# xytheta.net
KiCad netlist of a schematic drawn in EAGLE
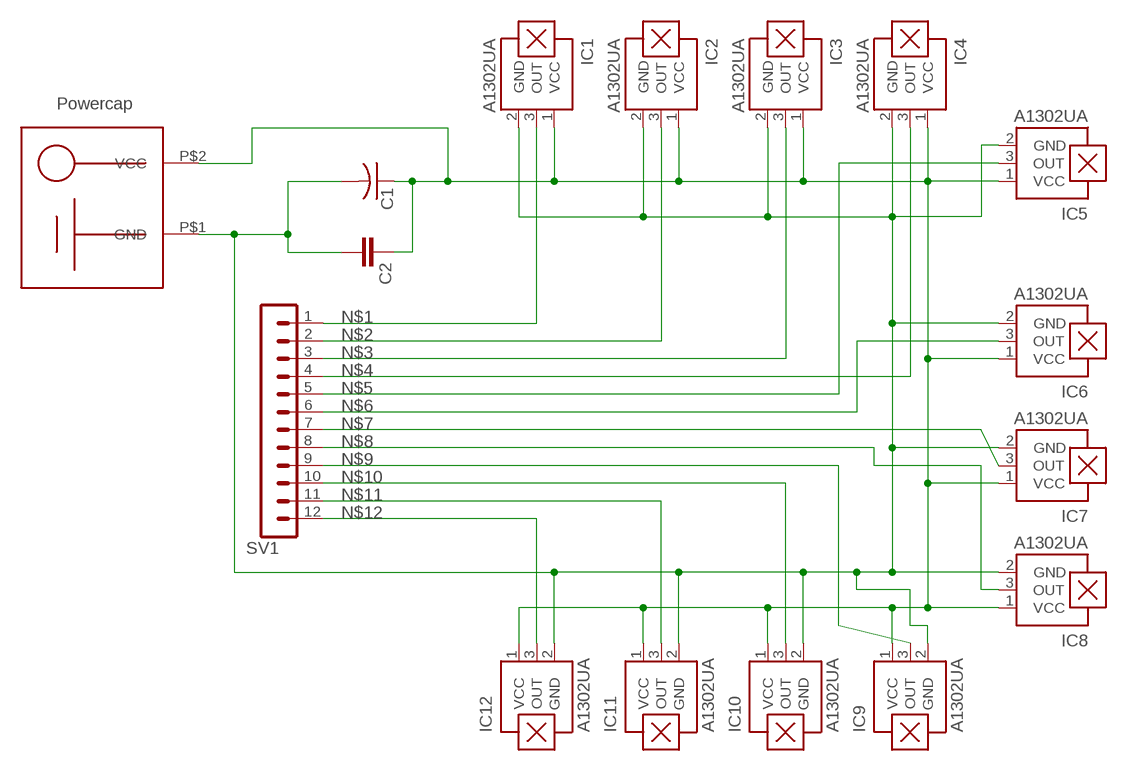
[diagram p0: schematic, sheet 1]

(export (version "E")
  (design (tool "Eeschema 10.0.6"))
  (components
    (comp (ref "C1")
      (value "C-US025-050X050")
      (footprint "eagle-import:C025-050X050")
      (libsource (lib "eagle-import") (part "C-US025-050X050"))
    )
    (comp (ref "C2")
      (value "C-EU025-025X050")
      (footprint "eagle-import:C025-025X050")
      (libsource (lib "eagle-import") (part "C-EU025-025X050"))
    )
    (comp (ref "IC1")
      (value "A1302UA")
      (footprint "eagle-import:SIP3-UA")
      (fields (field (name "MF") "ALLEGRO MICROSYSTEMS, INC.") (field (name "MPN") "A1302EUA-T"))
      (libsource (lib "eagle-import") (part "A13?UA02"))
    )
    (comp (ref "IC2")
      (value "A1302UA")
      (footprint "eagle-import:SIP3-UA")
      (fields (field (name "MF") "ALLEGRO MICROSYSTEMS, INC.") (field (name "MPN") "A1302EUA-T"))
      (libsource (lib "eagle-import") (part "A13?UA02"))
    )
    (comp (ref "IC3")
      (value "A1302UA")
      (footprint "eagle-import:SIP3-UA")
      (fields (field (name "MF") "ALLEGRO MICROSYSTEMS, INC.") (field (name "MPN") "A1302EUA-T"))
      (libsource (lib "eagle-import") (part "A13?UA02"))
    )
    (comp (ref "IC4")
      (value "A1302UA")
      (footprint "eagle-import:SIP3-UA")
      (fields (field (name "MF") "ALLEGRO MICROSYSTEMS, INC.") (field (name "MPN") "A1302EUA-T"))
      (libsource (lib "eagle-import") (part "A13?UA02"))
    )
    (comp (ref "IC5")
      (value "A1302UA")
      (footprint "eagle-import:SIP3-UA")
      (fields (field (name "MF") "ALLEGRO MICROSYSTEMS, INC.") (field (name "MPN") "A1302EUA-T"))
      (libsource (lib "eagle-import") (part "A13?UA02"))
    )
    (comp (ref "IC6")
      (value "A1302UA")
      (footprint "eagle-import:SIP3-UA")
      (fields (field (name "MF") "ALLEGRO MICROSYSTEMS, INC.") (field (name "MPN") "A1302EUA-T"))
      (libsource (lib "eagle-import") (part "A13?UA02"))
    )
    (comp (ref "IC7")
      (value "A1302UA")
      (footprint "eagle-import:SIP3-UA")
      (fields (field (name "MF") "ALLEGRO MICROSYSTEMS, INC.") (field (name "MPN") "A1302EUA-T"))
      (libsource (lib "eagle-import") (part "A13?UA02"))
    )
    (comp (ref "IC8")
      (value "A1302UA")
      (footprint "eagle-import:SIP3-UA")
      (fields (field (name "MF") "ALLEGRO MICROSYSTEMS, INC.") (field (name "MPN") "A1302EUA-T"))
      (libsource (lib "eagle-import") (part "A13?UA02"))
    )
    (comp (ref "IC9")
      (value "A1302UA")
      (footprint "eagle-import:SIP3-UA")
      (fields (field (name "MF") "ALLEGRO MICROSYSTEMS, INC.") (field (name "MPN") "A1302EUA-T"))
      (libsource (lib "eagle-import") (part "A13?UA02"))
    )
    (comp (ref "IC10")
      (value "A1302UA")
      (footprint "eagle-import:SIP3-UA")
      (fields (field (name "MF") "ALLEGRO MICROSYSTEMS, INC.") (field (name "MPN") "A1302EUA-T"))
      (libsource (lib "eagle-import") (part "A13?UA02"))
    )
    (comp (ref "IC11")
      (value "A1302UA")
      (footprint "eagle-import:SIP3-UA")
      (fields (field (name "MF") "ALLEGRO MICROSYSTEMS, INC.") (field (name "MPN") "A1302EUA-T"))
      (libsource (lib "eagle-import") (part "A13?UA02"))
    )
    (comp (ref "IC12")
      (value "A1302UA")
      (footprint "eagle-import:SIP3-UA")
      (fields (field (name "MF") "ALLEGRO MICROSYSTEMS, INC.") (field (name "MPN") "A1302EUA-T"))
      (libsource (lib "eagle-import") (part "A13?UA02"))
    )
    (comp (ref "SV1")
      (value "MA12-1")
      (footprint "eagle-import:MA12-1")
      (libsource (lib "eagle-import") (part "MA12-1"))
    )
    (comp (ref "U$1")
      (value "POWERCAP")
      (footprint "eagle-import:POWERCAP")
      (libsource (lib "eagle-import") (part "POWERCAP"))
    )
  )
  (nets
    (net (code "1") (name "/N$1") (class "Default")
      (node (ref "IC1") (pin "3") (pinfunction "OUT_3") (pintype "output"))
      (node (ref "SV1") (pin "1") (pinfunction "1_1") (pintype "passive"))
    )
    (net (code "2") (name "/N$2") (class "Default")
      (node (ref "IC2") (pin "3") (pinfunction "OUT_3") (pintype "output"))
      (node (ref "SV1") (pin "2") (pinfunction "2_2") (pintype "passive"))
    )
    (net (code "3") (name "/N$3") (class "Default")
      (node (ref "IC3") (pin "3") (pinfunction "OUT_3") (pintype "output"))
      (node (ref "SV1") (pin "3") (pinfunction "3_3") (pintype "passive"))
    )
    (net (code "4") (name "/N$4") (class "Default")
      (node (ref "IC4") (pin "3") (pinfunction "OUT_3") (pintype "output"))
      (node (ref "SV1") (pin "4") (pinfunction "4_4") (pintype "passive"))
    )
    (net (code "5") (name "/N$5") (class "Default")
      (node (ref "IC5") (pin "3") (pinfunction "OUT_3") (pintype "output"))
      (node (ref "SV1") (pin "5") (pinfunction "5_5") (pintype "passive"))
    )
    (net (code "6") (name "/N$6") (class "Default")
      (node (ref "IC6") (pin "3") (pinfunction "OUT_3") (pintype "output"))
      (node (ref "SV1") (pin "6") (pinfunction "6_6") (pintype "passive"))
    )
    (net (code "7") (name "/N$7") (class "Default")
      (node (ref "IC7") (pin "3") (pinfunction "OUT_3") (pintype "output"))
      (node (ref "SV1") (pin "7") (pinfunction "7_7") (pintype "passive"))
    )
    (net (code "8") (name "/N$8") (class "Default")
      (node (ref "IC8") (pin "3") (pinfunction "OUT_3") (pintype "output"))
      (node (ref "SV1") (pin "8") (pinfunction "8_8") (pintype "passive"))
    )
    (net (code "9") (name "/N$9") (class "Default")
      (node (ref "IC9") (pin "3") (pinfunction "OUT_3") (pintype "output"))
      (node (ref "SV1") (pin "9") (pinfunction "9_9") (pintype "passive"))
    )
    (net (code "10") (name "/N$10") (class "Default")
      (node (ref "IC10") (pin "3") (pinfunction "OUT_3") (pintype "output"))
      (node (ref "SV1") (pin "10") (pinfunction "10_10") (pintype "passive"))
    )
    (net (code "11") (name "/N$11") (class "Default")
      (node (ref "IC11") (pin "3") (pinfunction "OUT_3") (pintype "output"))
      (node (ref "SV1") (pin "11") (pinfunction "11_11") (pintype "passive"))
    )
    (net (code "12") (name "/N$12") (class "Default")
      (node (ref "IC12") (pin "3") (pinfunction "OUT_3") (pintype "output"))
      (node (ref "SV1") (pin "12") (pinfunction "12_12") (pintype "passive"))
    )
    (net (code "13") (name "Net-(IC1-GND)") (class "Default")
      (node (ref "C1") (pin "2") (pinfunction "2_2") (pintype "passive"))
      (node (ref "C2") (pin "2") (pinfunction "2_2") (pintype "passive"))
      (node (ref "IC1") (pin "2") (pinfunction "GND_2") (pintype "power_in"))
      (node (ref "IC10") (pin "2") (pinfunction "GND_2") (pintype "power_in"))
      (node (ref "IC11") (pin "2") (pinfunction "GND_2") (pintype "power_in"))
      (node (ref "IC12") (pin "2") (pinfunction "GND_2") (pintype "power_in"))
      (node (ref "IC2") (pin "2") (pinfunction "GND_2") (pintype "power_in"))
      (node (ref "IC3") (pin "2") (pinfunction "GND_2") (pintype "power_in"))
      (node (ref "IC4") (pin "2") (pinfunction "GND_2") (pintype "power_in"))
      (node (ref "IC5") (pin "2") (pinfunction "GND_2") (pintype "power_in"))
      (node (ref "IC6") (pin "2") (pinfunction "GND_2") (pintype "power_in"))
      (node (ref "IC7") (pin "2") (pinfunction "GND_2") (pintype "power_in"))
      (node (ref "IC8") (pin "2") (pinfunction "GND_2") (pintype "power_in"))
      (node (ref "IC9") (pin "2") (pinfunction "GND_2") (pintype "power_in"))
      (node (ref "U$1") (pin "P$1") (pinfunction "GND_P$1") (pintype "bidirectional"))
    )
    (net (code "14") (name "Net-(IC1-VCC)") (class "Default")
      (node (ref "C1") (pin "1") (pinfunction "1_1") (pintype "passive"))
      (node (ref "C2") (pin "1") (pinfunction "1_1") (pintype "passive"))
      (node (ref "IC1") (pin "1") (pinfunction "VCC_1") (pintype "power_in"))
      (node (ref "IC10") (pin "1") (pinfunction "VCC_1") (pintype "power_in"))
      (node (ref "IC11") (pin "1") (pinfunction "VCC_1") (pintype "power_in"))
      (node (ref "IC12") (pin "1") (pinfunction "VCC_1") (pintype "power_in"))
      (node (ref "IC2") (pin "1") (pinfunction "VCC_1") (pintype "power_in"))
      (node (ref "IC3") (pin "1") (pinfunction "VCC_1") (pintype "power_in"))
      (node (ref "IC4") (pin "1") (pinfunction "VCC_1") (pintype "power_in"))
      (node (ref "IC5") (pin "1") (pinfunction "VCC_1") (pintype "power_in"))
      (node (ref "IC6") (pin "1") (pinfunction "VCC_1") (pintype "power_in"))
      (node (ref "IC7") (pin "1") (pinfunction "VCC_1") (pintype "power_in"))
      (node (ref "IC8") (pin "1") (pinfunction "VCC_1") (pintype "power_in"))
      (node (ref "IC9") (pin "1") (pinfunction "VCC_1") (pintype "power_in"))
      (node (ref "U$1") (pin "P$2") (pinfunction "VCC_P$2") (pintype "bidirectional"))
    )
  )
)
